# SHT31.net
KiCad netlist of a schematic drawn in EAGLE
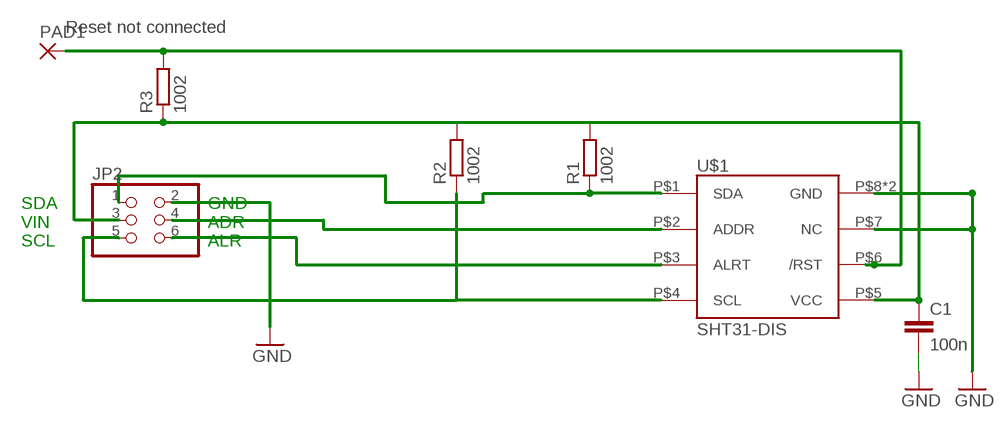
[diagram p0: schematic, sheet 1]

(export (version "E")
  (design (tool "Eeschema 10.0.6"))
  (components
    (comp (ref "C1")
      (value "100n")
      (footprint "eagle-import:C0805K")
      (libsource (lib "eagle-import") (part "C-EUC0805K"))
    )
    (comp (ref "JP2")
      (value "PINHD-2X3")
      (footprint "eagle-import:2X03")
      (libsource (lib "eagle-import") (part "PINHD-2X3"))
    )
    (comp (ref "PAD1")
      (value "1,6/0,8")
      (footprint "eagle-import:1,6_0,8")
      (libsource (lib "eagle-import") (part "1,6/0,8"))
    )
    (comp (ref "R1")
      (value "1002")
      (footprint "eagle-import:R0805")
      (libsource (lib "eagle-import") (part "R-EU_R0805"))
    )
    (comp (ref "R2")
      (value "1002")
      (footprint "eagle-import:R0805")
      (libsource (lib "eagle-import") (part "R-EU_R0805"))
    )
    (comp (ref "R3")
      (value "1002")
      (footprint "eagle-import:R0805")
      (libsource (lib "eagle-import") (part "R-EU_R0805"))
    )
    (comp (ref "U$1")
      (value "SHT31-DIS")
      (footprint "eagle-import:SHT3X")
      (libsource (lib "eagle-import") (part "SHT31-DIS"))
    )
  )
  (nets
    (net (code "1") (name "GND") (class "Default")
      (node (ref "C1") (pin "2") (pinfunction "2_2") (pintype "passive"))
      (node (ref "JP2") (pin "2") (pinfunction "2_2") (pintype "passive"))
      (node (ref "U$1") (pin "P$7") (pinfunction "NC_P$7") (pintype "bidirectional"))
      (node (ref "U$1") (pin "P$8") (pinfunction "GND_P$8") (pintype "bidirectional"))
      (node (ref "U$1") (pin "PAD") (pinfunction "GND_PAD") (pintype "bidirectional"))
    )
    (net (code "2") (name "Net-(PAD1-P)") (class "Default")
      (node (ref "PAD1") (pin "1") (pinfunction "P_1") (pintype "passive"))
      (node (ref "R3") (pin "2") (pinfunction "2_2") (pintype "passive"))
      (node (ref "U$1") (pin "P$6") (pinfunction "/RST_P$6") (pintype "bidirectional"))
    )
    (net (code "3") (name "Net-(U$1-ADDR)") (class "Default")
      (node (ref "JP2") (pin "4") (pinfunction "4_4") (pintype "passive"))
      (node (ref "U$1") (pin "P$2") (pinfunction "ADDR_P$2") (pintype "bidirectional"))
    )
    (net (code "4") (name "Net-(U$1-ALRT)") (class "Default")
      (node (ref "JP2") (pin "6") (pinfunction "6_6") (pintype "passive"))
      (node (ref "U$1") (pin "P$3") (pinfunction "ALRT_P$3") (pintype "bidirectional"))
    )
    (net (code "5") (name "Net-(U$1-SCL)") (class "Default")
      (node (ref "JP2") (pin "5") (pinfunction "5_5") (pintype "passive"))
      (node (ref "R2") (pin "1") (pinfunction "1_1") (pintype "passive"))
      (node (ref "U$1") (pin "P$4") (pinfunction "SCL_P$4") (pintype "bidirectional"))
    )
    (net (code "6") (name "Net-(U$1-SDA)") (class "Default")
      (node (ref "JP2") (pin "1") (pinfunction "1_1") (pintype "passive"))
      (node (ref "R1") (pin "1") (pinfunction "1_1") (pintype "passive"))
      (node (ref "U$1") (pin "P$1") (pinfunction "SDA_P$1") (pintype "bidirectional"))
    )
    (net (code "7") (name "Net-(U$1-VCC)") (class "Default")
      (node (ref "C1") (pin "1") (pinfunction "1_1") (pintype "passive"))
      (node (ref "JP2") (pin "3") (pinfunction "3_3") (pintype "passive"))
      (node (ref "R1") (pin "2") (pinfunction "2_2") (pintype "passive"))
      (node (ref "R2") (pin "2") (pinfunction "2_2") (pintype "passive"))
      (node (ref "R3") (pin "1") (pinfunction "1_1") (pintype "passive"))
      (node (ref "U$1") (pin "P$5") (pinfunction "VCC_P$5") (pintype "bidirectional"))
    )
  )
)
